# Sheet1.net
KiCad netlist of a schematic drawn in Altium Designer
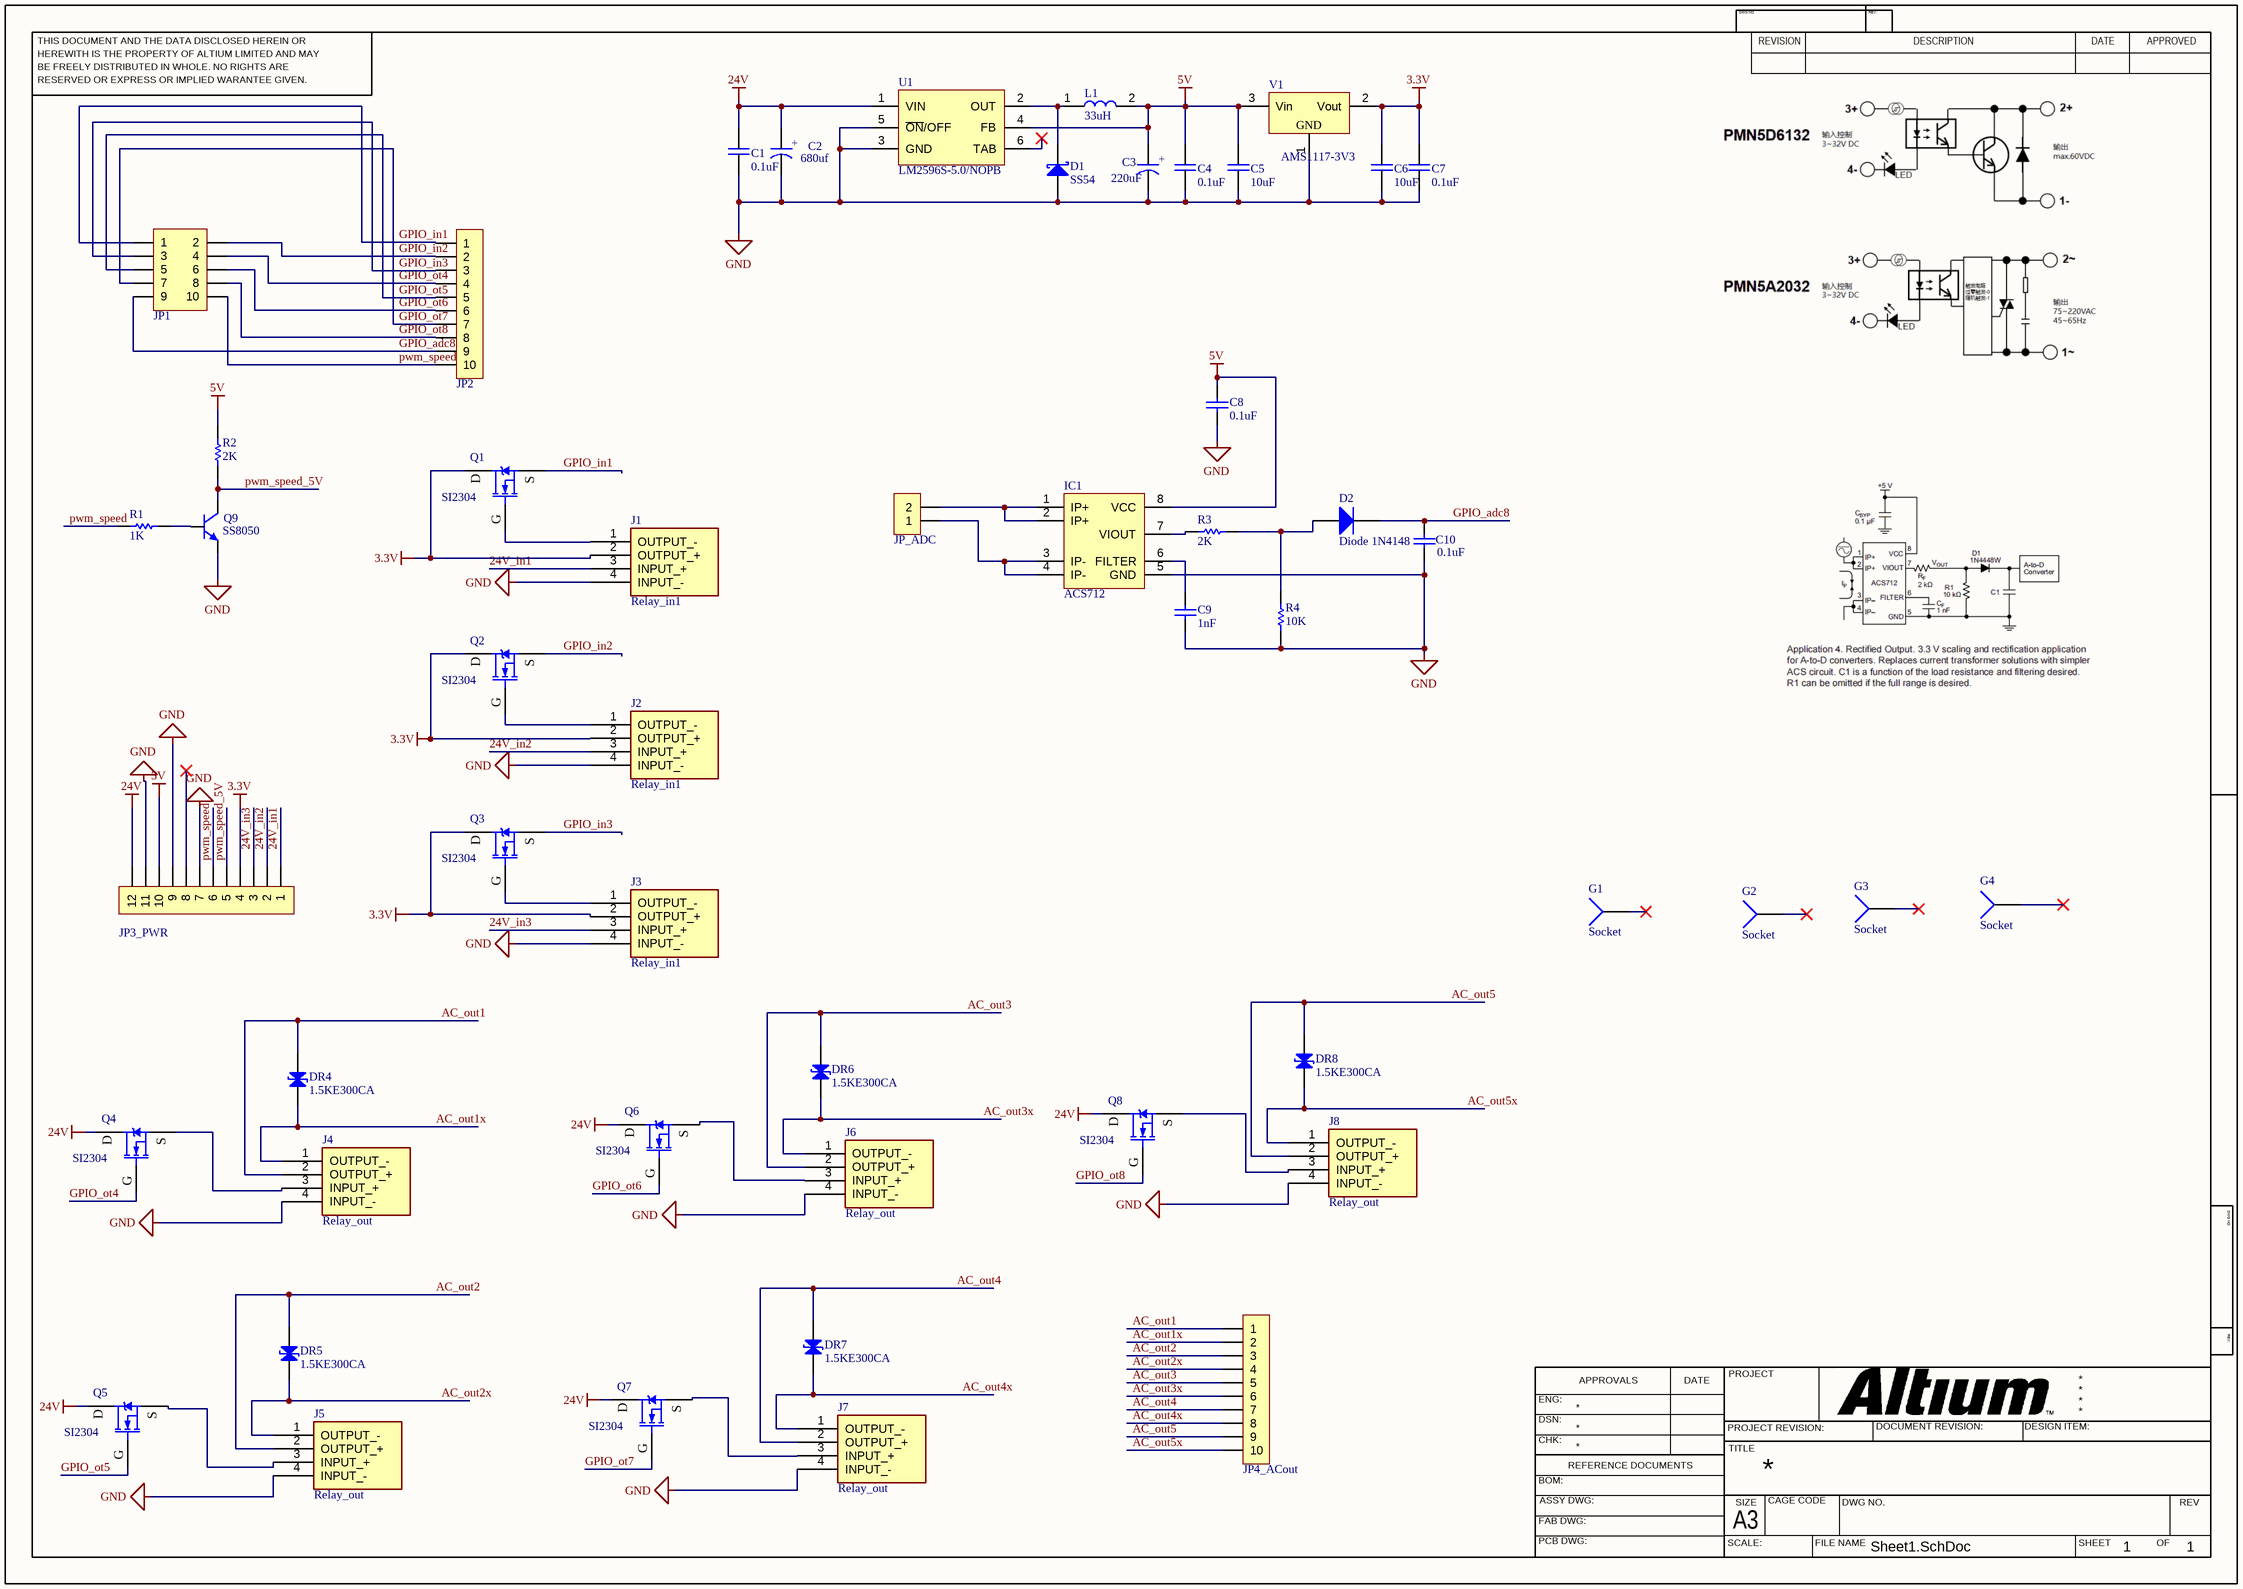
[diagram p0: Sheet1.SchDoc]

(export (version "E")
  (design (tool "Eeschema 10.0.6"))
  (components
    (comp (ref "C1") (value "0.1uF") (footprint "C 0805_M") (libsource (lib "LM2596S_5.0") (part "CAP-SMT")))
    (comp (ref "C2")
      (value "680uf")
      (footprint "CAP 5.0*12.5*20")
      (description "CAP-SMD")
      (libsource (lib "LM2596S_5.0") (part "CAP-SMD"))
    )
    (comp (ref "C3")
      (value "220uF")
      (footprint "CAP 5.0*10*16")
      (description "CAP-SMD")
      (libsource (lib "LM2596S_5.0") (part "CAP-SMD"))
    )
    (comp (ref "C4") (value "0.1uF") (footprint "C 0805_M") (libsource (lib "LM2596S_5.0") (part "CAP-SMT")))
    (comp (ref "C5") (value "10uF") (footprint "C 0805_M") (libsource (lib "LM2596S_5.0") (part "CAP-SMT")))
    (comp (ref "C6") (value "10uF") (footprint "C 0805_M") (libsource (lib "LM2596S_5.0") (part "CAP-SMT")))
    (comp (ref "C7") (value "0.1uF") (footprint "C 0805_M") (libsource (lib "LM2596S_5.0") (part "CAP-SMT")))
    (comp (ref "C8")
      (value "0.1uF")
      (footprint "C 0805_M")
      (description "Capacitor")
      (fields (field (name "PUBLISHER") "Altium Limited"))
      (libsource (lib "Miscellaneous Devices") (part "Cap"))
    )
    (comp (ref "C9")
      (value "1nF")
      (footprint "C 0805_M")
      (description "Capacitor")
      (fields (field (name "PUBLISHER") "Altium Limited"))
      (libsource (lib "Miscellaneous Devices") (part "Cap"))
    )
    (comp (ref "C10")
      (value "0.1uF")
      (footprint "C 0805_M")
      (description "Capacitor")
      (fields (field (name "PUBLISHER") "Altium Limited"))
      (libsource (lib "Miscellaneous Devices") (part "Cap"))
    )
    (comp (ref "D1") (value "SS54") (footprint "SMC") (libsource (lib "LM2596S_5.0") (part "DIO")))
    (comp (ref "D2")
      (value "Diode 1N4148")
      (footprint "SOD-123")
      (description "High Conductance Fast Diode")
      (fields (field (name "PUBLISHER") "Altium Limited"))
      (libsource (lib "Miscellaneous Devices") (part "Diode 1N4148"))
    )
    (comp (ref "DR4")
      (value "1.5KE300CA")
      (footprint "DO-15")
      (description "瞬态电压抑制二极管")
      (fields (field (name "版权归属") "源创客"))
      (libsource (lib "8.1   - 二极管-整流桥") (part "DR"))
    )
    (comp (ref "DR5")
      (value "1.5KE300CA")
      (footprint "DO-15")
      (description "瞬态电压抑制二极管")
      (fields (field (name "版权归属") "源创客"))
      (libsource (lib "8.1   - 二极管-整流桥") (part "DR"))
    )
    (comp (ref "DR6")
      (value "1.5KE300CA")
      (footprint "DO-15")
      (description "瞬态电压抑制二极管")
      (fields (field (name "版权归属") "源创客"))
      (libsource (lib "8.1   - 二极管-整流桥") (part "DR"))
    )
    (comp (ref "DR7")
      (value "1.5KE300CA")
      (footprint "DO-15")
      (description "瞬态电压抑制二极管")
      (fields (field (name "版权归属") "源创客"))
      (libsource (lib "8.1   - 二极管-整流桥") (part "DR"))
    )
    (comp (ref "DR8")
      (value "1.5KE300CA")
      (footprint "DO-15")
      (description "瞬态电压抑制二极管")
      (fields (field (name "版权归属") "源创客"))
      (libsource (lib "8.1   - 二极管-整流桥") (part "DR"))
    )
    (comp (ref "G1")
      (value "Socket")
      (footprint "M3x6_L")
      (fields (field (name "PUBLISHER") "Altium Limited"))
      (libsource (lib "Miscellaneous Connectors") (part "Socket"))
    )
    (comp (ref "G2")
      (value "Socket")
      (footprint "M3x6_L")
      (fields (field (name "PUBLISHER") "Altium Limited"))
      (libsource (lib "Miscellaneous Connectors") (part "Socket"))
    )
    (comp (ref "G3")
      (value "Socket")
      (footprint "M3x6_L")
      (fields (field (name "PUBLISHER") "Altium Limited"))
      (libsource (lib "Miscellaneous Connectors") (part "Socket"))
    )
    (comp (ref "G4")
      (value "Socket")
      (footprint "M3x6_L")
      (fields (field (name "PUBLISHER") "Altium Limited"))
      (libsource (lib "Miscellaneous Connectors") (part "Socket"))
    )
    (comp (ref "IC1")
      (value "ACS712")
      (footprint "SOP8_M")
      (description "电流检测芯片")
      (fields (field (name "版权归属") "源创客"))
      (libsource (lib "1.1   - IC芯片") (part "ACS712"))
    )
    (comp (ref "J1")
      (value "Relay_in1")
      (footprint "2982647")
      (description "Connector")
      (fields
        (field (name "MANUFACTURER_PART_NUMBER") "2982647")
        (field (name "MOUSER PART NUMBER") "651-2982647")
      )
      (libsource (lib "SSR") (part "2982647"))
    )
    (comp (ref "J2")
      (value "Relay_in1")
      (footprint "2982647")
      (description "Connector")
      (fields
        (field (name "MANUFACTURER_PART_NUMBER") "2982647")
        (field (name "MOUSER PART NUMBER") "651-2982647")
      )
      (libsource (lib "SSR") (part "2982647"))
    )
    (comp (ref "J3")
      (value "Relay_in1")
      (footprint "2982647")
      (description "Connector")
      (fields
        (field (name "MANUFACTURER_PART_NUMBER") "2982647")
        (field (name "MOUSER PART NUMBER") "651-2982647")
      )
      (libsource (lib "SSR") (part "2982647"))
    )
    (comp (ref "J4")
      (value "Relay_out")
      (footprint "2982647")
      (description "Connector")
      (fields
        (field (name "MANUFACTURER_PART_NUMBER") "2982647")
        (field (name "MOUSER PART NUMBER") "651-2982647")
      )
      (libsource (lib "SSR") (part "2982647"))
    )
    (comp (ref "J5")
      (value "Relay_out")
      (footprint "2982647")
      (description "Connector")
      (fields
        (field (name "MANUFACTURER_PART_NUMBER") "2982647")
        (field (name "MOUSER PART NUMBER") "651-2982647")
      )
      (libsource (lib "SSR") (part "2982647"))
    )
    (comp (ref "J6")
      (value "Relay_out")
      (footprint "2982647")
      (description "Connector")
      (fields
        (field (name "MANUFACTURER_PART_NUMBER") "2982647")
        (field (name "MOUSER PART NUMBER") "651-2982647")
      )
      (libsource (lib "SSR") (part "2982647"))
    )
    (comp (ref "J7")
      (value "Relay_out")
      (footprint "2982647")
      (description "Connector")
      (fields
        (field (name "MANUFACTURER_PART_NUMBER") "2982647")
        (field (name "MOUSER PART NUMBER") "651-2982647")
      )
      (libsource (lib "SSR") (part "2982647"))
    )
    (comp (ref "J8")
      (value "Relay_out")
      (footprint "2982647")
      (description "Connector")
      (fields
        (field (name "MANUFACTURER_PART_NUMBER") "2982647")
        (field (name "MOUSER PART NUMBER") "651-2982647")
      )
      (libsource (lib "") (part "2982647_1"))
    )
    (comp (ref "JP1")
      (value "Header 5X2")
      (footprint "IDC2.54-LI-2x5P")
      (description "5*2P接插件")
      (fields (field (name "版权归属") "源创客"))
      (libsource (lib "4.5   - 接插件-脚距2.54") (part "Header 5X2"))
    )
    (comp (ref "JP2")
      (value "HDR-1X10")
      (footprint "KF128-3.81-10P")
      (description "10P接插件")
      (fields (field (name "版权归属") "源创客"))
      (libsource (lib "4.6   - 接插件-脚距3.5") (part "Header 10"))
    )
    (comp (ref "JP3_PWR")
      (value "HDR-1X12")
      (footprint "KF128-3.81-12P")
      (description "12P接插件")
      (fields (field (name "版权归属") "源创客"))
      (libsource (lib "4.7   - 接插件-脚距3.81") (part "Header 12"))
    )
    (comp (ref "JP4_ACout")
      (value "HDR-1X10")
      (footprint "KF128-3.81-10P")
      (description "10P接插件")
      (fields (field (name "版权归属") "源创客"))
      (libsource (lib "4.6   - 接插件-脚距3.5") (part "Header 10"))
    )
    (comp (ref "JP_ADC")
      (value "HDR-1X2")
      (footprint "KF128-3.81-2P")
      (description "2P接插件")
      (fields (field (name "版权归属") "源创客"))
      (libsource (lib "4.7   - 接插件-脚距3.81") (part "Header 2"))
    )
    (comp (ref "L1") (value "33uH") (footprint "CDRH74") (libsource (lib "LM2596S_5.0") (part "L-CDRH74")))
    (comp (ref "Q1")
      (value "SI2304")
      (footprint "SOT23-3M")
      (description "N沟道场效应管")
      (fields (field (name "版权归属") "源创客"))
      (libsource (lib "6.1   - 场效应管-可控硅") (part "SI2302"))
    )
    (comp (ref "Q2")
      (value "SI2304")
      (footprint "SOT23-3M")
      (description "N沟道场效应管")
      (fields (field (name "版权归属") "源创客"))
      (libsource (lib "6.1   - 场效应管-可控硅") (part "SI2302"))
    )
    (comp (ref "Q3")
      (value "SI2304")
      (footprint "SOT23-3M")
      (description "N沟道场效应管")
      (fields (field (name "版权归属") "源创客"))
      (libsource (lib "6.1   - 场效应管-可控硅") (part "SI2302"))
    )
    (comp (ref "Q4")
      (value "SI2304")
      (footprint "SOT23-3M")
      (description "N沟道场效应管")
      (fields (field (name "版权归属") "源创客"))
      (libsource (lib "6.1   - 场效应管-可控硅") (part "SI2302"))
    )
    (comp (ref "Q5")
      (value "SI2304")
      (footprint "SOT23-3M")
      (description "N沟道场效应管")
      (fields (field (name "版权归属") "源创客"))
      (libsource (lib "6.1   - 场效应管-可控硅") (part "SI2302"))
    )
    (comp (ref "Q6")
      (value "SI2304")
      (footprint "SOT23-3M")
      (description "N沟道场效应管")
      (fields (field (name "版权归属") "源创客"))
      (libsource (lib "6.1   - 场效应管-可控硅") (part "SI2302"))
    )
    (comp (ref "Q7")
      (value "SI2304")
      (footprint "SOT23-3M")
      (description "N沟道场效应管")
      (fields (field (name "版权归属") "源创客"))
      (libsource (lib "6.1   - 场效应管-可控硅") (part "SI2302"))
    )
    (comp (ref "Q8")
      (value "SI2304")
      (footprint "SOT23-3M")
      (description "N沟道场效应管")
      (fields (field (name "版权归属") "源创客"))
      (libsource (lib "6.1   - 场效应管-可控硅") (part "SI2302"))
    )
    (comp (ref "Q9")
      (value "SS8050")
      (footprint "TO92A")
      (description "高频放大-NPN型")
      (fields (field (name "版权归属") "源创客"))
      (libsource (lib "6.2   - 三极管") (part "8050-DIP"))
    )
    (comp (ref "R1")
      (value "1K")
      (footprint "R 0805_M")
      (description "Resistor")
      (fields (field (name "PUBLISHER") "Altium Limited"))
      (libsource (lib "Miscellaneous Devices") (part "Res1"))
    )
    (comp (ref "R2")
      (value "2K")
      (footprint "R 0805_M")
      (description "Resistor")
      (fields (field (name "PUBLISHER") "Altium Limited"))
      (libsource (lib "Miscellaneous Devices") (part "Res1"))
    )
    (comp (ref "R3")
      (value "2K")
      (footprint "R 0805_M")
      (description "Resistor")
      (fields (field (name "PUBLISHER") "Altium Limited"))
      (libsource (lib "Miscellaneous Devices") (part "Res1"))
    )
    (comp (ref "R4")
      (value "10K")
      (footprint "R 0805_M")
      (description "Resistor")
      (fields (field (name "PUBLISHER") "Altium Limited"))
      (libsource (lib "Miscellaneous Devices") (part "Res1"))
    )
    (comp (ref "U1")
      (value "LM2596S-5.0/NOPB")
      (footprint "TO263-5A")
      (description "SIMPLE SWITCHER® Power Converter 150 KHz 3A Step-Down Voltage Regulator, 5-pin TO-263, Pb-Free")
      (fields (field (name "MANUFACTURER") "Texas Instruments"))
      (libsource (lib "LM2596S_5.0") (part "LM2596S-5.0"))
    )
    (comp (ref "V1")
      (value "AMS1117-3V3")
      (footprint "SOT223_M")
      (description "三端稳压芯片")
      (fields (field (name "版权归属") "源创客"))
      (libsource (lib "1.3   - 电源类芯片") (part "AMS1117"))
    )
  )
  (nets
    (net (code "1") (name "/24V_in1") (class "Default")
      (node (ref "J1") (pin "3") (pinfunction "INPUT_+_3") (pintype "passive"))
      (node (ref "JP3_PWR") (pin "1") (pinfunction "1_1") (pintype "passive"))
    )
    (net (code "2") (name "/24V_in2") (class "Default")
      (node (ref "J2") (pin "3") (pinfunction "INPUT_+_3") (pintype "passive"))
      (node (ref "JP3_PWR") (pin "2") (pinfunction "2_2") (pintype "passive"))
    )
    (net (code "3") (name "/24V_in3") (class "Default")
      (node (ref "J3") (pin "3") (pinfunction "INPUT_+_3") (pintype "passive"))
      (node (ref "JP3_PWR") (pin "3") (pinfunction "3_3") (pintype "passive"))
    )
    (net (code "4") (name "/AC_out1") (class "Default")
      (node (ref "DR4") (pin "1") (pinfunction "A_1") (pintype "passive"))
      (node (ref "J4") (pin "2") (pinfunction "OUTPUT_+_2") (pintype "passive"))
      (node (ref "JP4_ACout") (pin "1") (pinfunction "1_1") (pintype "passive"))
    )
    (net (code "5") (name "/AC_out1x") (class "Default")
      (node (ref "DR4") (pin "2") (pinfunction "K_2") (pintype "passive"))
      (node (ref "J4") (pin "1") (pinfunction "OUTPUT_-_1") (pintype "passive"))
      (node (ref "JP4_ACout") (pin "2") (pinfunction "2_2") (pintype "passive"))
    )
    (net (code "6") (name "/AC_out2") (class "Default")
      (node (ref "DR5") (pin "1") (pinfunction "A_1") (pintype "passive"))
      (node (ref "J5") (pin "2") (pinfunction "OUTPUT_+_2") (pintype "passive"))
      (node (ref "JP4_ACout") (pin "3") (pinfunction "3_3") (pintype "passive"))
    )
    (net (code "7") (name "/AC_out2x") (class "Default")
      (node (ref "DR5") (pin "2") (pinfunction "K_2") (pintype "passive"))
      (node (ref "J5") (pin "1") (pinfunction "OUTPUT_-_1") (pintype "passive"))
      (node (ref "JP4_ACout") (pin "4") (pinfunction "4_4") (pintype "passive"))
    )
    (net (code "8") (name "/AC_out3") (class "Default")
      (node (ref "DR6") (pin "1") (pinfunction "A_1") (pintype "passive"))
      (node (ref "J6") (pin "2") (pinfunction "OUTPUT_+_2") (pintype "passive"))
      (node (ref "JP4_ACout") (pin "5") (pinfunction "5_5") (pintype "passive"))
    )
    (net (code "9") (name "/AC_out3x") (class "Default")
      (node (ref "DR6") (pin "2") (pinfunction "K_2") (pintype "passive"))
      (node (ref "J6") (pin "1") (pinfunction "OUTPUT_-_1") (pintype "passive"))
      (node (ref "JP4_ACout") (pin "6") (pinfunction "6_6") (pintype "passive"))
    )
    (net (code "10") (name "/AC_out4") (class "Default")
      (node (ref "DR7") (pin "1") (pinfunction "A_1") (pintype "passive"))
      (node (ref "J7") (pin "2") (pinfunction "OUTPUT_+_2") (pintype "passive"))
      (node (ref "JP4_ACout") (pin "7") (pinfunction "7_7") (pintype "passive"))
    )
    (net (code "11") (name "/AC_out4x") (class "Default")
      (node (ref "DR7") (pin "2") (pinfunction "K_2") (pintype "passive"))
      (node (ref "J7") (pin "1") (pinfunction "OUTPUT_-_1") (pintype "passive"))
      (node (ref "JP4_ACout") (pin "8") (pinfunction "8_8") (pintype "passive"))
    )
    (net (code "12") (name "/AC_out5") (class "Default")
      (node (ref "DR8") (pin "1") (pinfunction "A_1") (pintype "passive"))
      (node (ref "J8") (pin "2") (pinfunction "OUTPUT_+_2") (pintype "passive"))
      (node (ref "JP4_ACout") (pin "9") (pinfunction "9_9") (pintype "passive"))
    )
    (net (code "13") (name "/AC_out5x") (class "Default")
      (node (ref "DR8") (pin "2") (pinfunction "K_2") (pintype "passive"))
      (node (ref "J8") (pin "1") (pinfunction "OUTPUT_-_1") (pintype "passive"))
      (node (ref "JP4_ACout") (pin "10") (pinfunction "10_10") (pintype "passive"))
    )
    (net (code "14") (name "/GPIO_adc8") (class "Default")
      (node (ref "C10") (pin "2") (pinfunction "2_2") (pintype "passive"))
      (node (ref "D2") (pin "2") (pinfunction "K_2") (pintype "passive"))
      (node (ref "JP1") (pin "9") (pinfunction "9_9") (pintype "passive"))
      (node (ref "JP2") (pin "9") (pinfunction "9_9") (pintype "passive"))
    )
    (net (code "15") (name "/GPIO_in1") (class "Default")
      (node (ref "JP1") (pin "1") (pinfunction "1_1") (pintype "passive"))
      (node (ref "JP2") (pin "1") (pinfunction "1_1") (pintype "passive"))
      (node (ref "Q1") (pin "2") (pinfunction "S_2") (pintype "passive"))
    )
    (net (code "16") (name "/GPIO_in2") (class "Default")
      (node (ref "JP1") (pin "2") (pinfunction "2_2") (pintype "passive"))
      (node (ref "JP2") (pin "2") (pinfunction "2_2") (pintype "passive"))
      (node (ref "Q2") (pin "2") (pinfunction "S_2") (pintype "passive"))
    )
    (net (code "17") (name "/GPIO_in3") (class "Default")
      (node (ref "JP1") (pin "3") (pinfunction "3_3") (pintype "passive"))
      (node (ref "JP2") (pin "3") (pinfunction "3_3") (pintype "passive"))
      (node (ref "Q3") (pin "2") (pinfunction "S_2") (pintype "passive"))
    )
    (net (code "18") (name "/GPIO_ot4") (class "Default")
      (node (ref "JP1") (pin "4") (pinfunction "4_4") (pintype "passive"))
      (node (ref "JP2") (pin "4") (pinfunction "4_4") (pintype "passive"))
      (node (ref "Q4") (pin "1") (pinfunction "G_1") (pintype "passive"))
    )
    (net (code "19") (name "/GPIO_ot5") (class "Default")
      (node (ref "JP1") (pin "5") (pinfunction "5_5") (pintype "passive"))
      (node (ref "JP2") (pin "5") (pinfunction "5_5") (pintype "passive"))
      (node (ref "Q5") (pin "1") (pinfunction "G_1") (pintype "passive"))
    )
    (net (code "20") (name "/GPIO_ot6") (class "Default")
      (node (ref "JP1") (pin "6") (pinfunction "6_6") (pintype "passive"))
      (node (ref "JP2") (pin "6") (pinfunction "6_6") (pintype "passive"))
      (node (ref "Q6") (pin "1") (pinfunction "G_1") (pintype "passive"))
    )
    (net (code "21") (name "/GPIO_ot7") (class "Default")
      (node (ref "JP1") (pin "7") (pinfunction "7_7") (pintype "passive"))
      (node (ref "JP2") (pin "7") (pinfunction "7_7") (pintype "passive"))
      (node (ref "Q7") (pin "1") (pinfunction "G_1") (pintype "passive"))
    )
    (net (code "22") (name "/GPIO_ot8") (class "Default")
      (node (ref "JP1") (pin "8") (pinfunction "8_8") (pintype "passive"))
      (node (ref "JP2") (pin "8") (pinfunction "8_8") (pintype "passive"))
      (node (ref "Q8") (pin "1") (pinfunction "G_1") (pintype "passive"))
    )
    (net (code "23") (name "/pwm_speed") (class "Default")
      (node (ref "JP1") (pin "10") (pinfunction "10_10") (pintype "passive"))
      (node (ref "JP2") (pin "10") (pinfunction "10_10") (pintype "passive"))
      (node (ref "JP3_PWR") (pin "6") (pinfunction "6_6") (pintype "passive"))
      (node (ref "R1") (pin "1") (pinfunction "1_1") (pintype "passive"))
    )
    (net (code "24") (name "/pwm_speed_5V") (class "Default")
      (node (ref "JP3_PWR") (pin "5") (pinfunction "5_5") (pintype "passive"))
      (node (ref "Q9") (pin "3") (pinfunction "C_3") (pintype "passive"))
      (node (ref "R2") (pin "1") (pinfunction "1_1") (pintype "passive"))
    )
    (net (code "25") (name "3.3V") (class "Default")
      (node (ref "C6") (pin "2") (pinfunction "2_2") (pintype "passive"))
      (node (ref "C7") (pin "2") (pinfunction "2_2") (pintype "passive"))
      (node (ref "J1") (pin "2") (pinfunction "OUTPUT_+_2") (pintype "passive"))
      (node (ref "J2") (pin "2") (pinfunction "OUTPUT_+_2") (pintype "passive"))
      (node (ref "J3") (pin "2") (pinfunction "OUTPUT_+_2") (pintype "passive"))
      (node (ref "JP3_PWR") (pin "4") (pinfunction "4_4") (pintype "passive"))
      (node (ref "Q1") (pin "3") (pinfunction "D_3") (pintype "passive"))
      (node (ref "Q2") (pin "3") (pinfunction "D_3") (pintype "passive"))
      (node (ref "Q3") (pin "3") (pinfunction "D_3") (pintype "passive"))
      (node (ref "V1") (pin "2") (pinfunction "Vout_2") (pintype "passive"))
    )
    (net (code "26") (name "5V") (class "Default")
      (node (ref "C3") (pin "2") (pinfunction "2_2") (pintype "passive"))
      (node (ref "C4") (pin "2") (pinfunction "2_2") (pintype "passive"))
      (node (ref "C5") (pin "2") (pinfunction "2_2") (pintype "passive"))
      (node (ref "C8") (pin "2") (pinfunction "2_2") (pintype "passive"))
      (node (ref "IC1") (pin "8") (pinfunction "VCC_8") (pintype "passive"))
      (node (ref "JP3_PWR") (pin "10") (pinfunction "10_10") (pintype "passive"))
      (node (ref "L1") (pin "2") (pinfunction "2_2") (pintype "passive"))
      (node (ref "R2") (pin "2") (pinfunction "2_2") (pintype "passive"))
      (node (ref "U1") (pin "4") (pinfunction "FB_4") (pintype "passive"))
      (node (ref "V1") (pin "3") (pinfunction "Vin_3") (pintype "passive"))
    )
    (net (code "27") (name "24V") (class "Default")
      (node (ref "C1") (pin "2") (pinfunction "2_2") (pintype "passive"))
      (node (ref "C2") (pin "2") (pinfunction "2_2") (pintype "passive"))
      (node (ref "JP3_PWR") (pin "12") (pinfunction "12_12") (pintype "passive"))
      (node (ref "Q4") (pin "3") (pinfunction "D_3") (pintype "passive"))
      (node (ref "Q5") (pin "3") (pinfunction "D_3") (pintype "passive"))
      (node (ref "Q6") (pin "3") (pinfunction "D_3") (pintype "passive"))
      (node (ref "Q7") (pin "3") (pinfunction "D_3") (pintype "passive"))
      (node (ref "Q8") (pin "3") (pinfunction "D_3") (pintype "passive"))
      (node (ref "U1") (pin "1") (pinfunction "VIN_1") (pintype "power_in"))
    )
    (net (code "28") (name "GND") (class "Default")
      (node (ref "C1") (pin "1") (pinfunction "1_1") (pintype "passive"))
      (node (ref "C10") (pin "1") (pinfunction "1_1") (pintype "passive"))
      (node (ref "C2") (pin "1") (pinfunction "1_1") (pintype "passive"))
      (node (ref "C3") (pin "1") (pinfunction "1_1") (pintype "passive"))
      (node (ref "C4") (pin "1") (pinfunction "1_1") (pintype "passive"))
      (node (ref "C5") (pin "1") (pinfunction "1_1") (pintype "passive"))
      (node (ref "C6") (pin "1") (pinfunction "1_1") (pintype "passive"))
      (node (ref "C7") (pin "1") (pinfunction "1_1") (pintype "passive"))
      (node (ref "C8") (pin "1") (pinfunction "1_1") (pintype "passive"))
      (node (ref "C9") (pin "1") (pinfunction "1_1") (pintype "passive"))
      (node (ref "D1") (pin "1") (pinfunction "1_1") (pintype "passive"))
      (node (ref "IC1") (pin "5") (pinfunction "GND_5") (pintype "passive"))
      (node (ref "J1") (pin "4") (pinfunction "INPUT_-_4") (pintype "passive"))
      (node (ref "J2") (pin "4") (pinfunction "INPUT_-_4") (pintype "passive"))
      (node (ref "J3") (pin "4") (pinfunction "INPUT_-_4") (pintype "passive"))
      (node (ref "J4") (pin "4") (pinfunction "INPUT_-_4") (pintype "passive"))
      (node (ref "J5") (pin "4") (pinfunction "INPUT_-_4") (pintype "passive"))
      (node (ref "J6") (pin "4") (pinfunction "INPUT_-_4") (pintype "passive"))
      (node (ref "J7") (pin "4") (pinfunction "INPUT_-_4") (pintype "passive"))
      (node (ref "J8") (pin "4") (pinfunction "INPUT_-_4") (pintype "passive"))
      (node (ref "JP3_PWR") (pin "11") (pinfunction "11_11") (pintype "passive"))
      (node (ref "JP3_PWR") (pin "7") (pinfunction "7_7") (pintype "passive"))
      (node (ref "JP3_PWR") (pin "9") (pinfunction "9_9") (pintype "passive"))
      (node (ref "Q9") (pin "1") (pinfunction "E_1") (pintype "passive"))
      (node (ref "R4") (pin "1") (pinfunction "1_1") (pintype "passive"))
      (node (ref "U1") (pin "3") (pinfunction "GND_3") (pintype "power_in"))
      (node (ref "U1") (pin "5") (pinfunction "~{ON}/OFF_5") (pintype "passive"))
      (node (ref "V1") (pin "1") (pinfunction "GND_1") (pintype "passive"))
    )
    (net (code "29") (name "Net-(D2-A)") (class "Default")
      (node (ref "D2") (pin "1") (pinfunction "A_1") (pintype "passive"))
      (node (ref "R3") (pin "2") (pinfunction "2_2") (pintype "passive"))
      (node (ref "R4") (pin "2") (pinfunction "2_2") (pintype "passive"))
    )
    (net (code "30") (name "Net-(IC1-FILTER)") (class "Default")
      (node (ref "C9") (pin "2") (pinfunction "2_2") (pintype "passive"))
      (node (ref "IC1") (pin "6") (pinfunction "FILTER_6") (pintype "passive"))
    )
    (net (code "31") (name "Net-(IC1-IP+-Pad1)") (class "Default")
      (node (ref "IC1") (pin "1") (pinfunction "IP+_1") (pintype "passive"))
      (node (ref "IC1") (pin "2") (pinfunction "IP+_2") (pintype "passive"))
      (node (ref "JP_ADC") (pin "2") (pinfunction "2_2") (pintype "passive"))
    )
    (net (code "32") (name "Net-(IC1-IP--Pad3)") (class "Default")
      (node (ref "IC1") (pin "3") (pinfunction "IP-_3") (pintype "passive"))
      (node (ref "IC1") (pin "4") (pinfunction "IP-_4") (pintype "passive"))
      (node (ref "JP_ADC") (pin "1") (pinfunction "1_1") (pintype "passive"))
    )
    (net (code "33") (name "Net-(IC1-VIOUT)") (class "Default")
      (node (ref "IC1") (pin "7") (pinfunction "VIOUT_7") (pintype "passive"))
      (node (ref "R3") (pin "1") (pinfunction "1_1") (pintype "passive"))
    )
    (net (code "34") (name "Net-(J1-OUTPUT_-)") (class "Default")
      (node (ref "J1") (pin "1") (pinfunction "OUTPUT_-_1") (pintype "passive"))
      (node (ref "Q1") (pin "1") (pinfunction "G_1") (pintype "passive"))
    )
    (net (code "35") (name "Net-(J2-OUTPUT_-)") (class "Default")
      (node (ref "J2") (pin "1") (pinfunction "OUTPUT_-_1") (pintype "passive"))
      (node (ref "Q2") (pin "1") (pinfunction "G_1") (pintype "passive"))
    )
    (net (code "36") (name "Net-(J3-OUTPUT_-)") (class "Default")
      (node (ref "J3") (pin "1") (pinfunction "OUTPUT_-_1") (pintype "passive"))
      (node (ref "Q3") (pin "1") (pinfunction "G_1") (pintype "passive"))
    )
    (net (code "37") (name "Net-(J4-INPUT_+)") (class "Default")
      (node (ref "J4") (pin "3") (pinfunction "INPUT_+_3") (pintype "passive"))
      (node (ref "Q4") (pin "2") (pinfunction "S_2") (pintype "passive"))
    )
    (net (code "38") (name "Net-(J5-INPUT_+)") (class "Default")
      (node (ref "J5") (pin "3") (pinfunction "INPUT_+_3") (pintype "passive"))
      (node (ref "Q5") (pin "2") (pinfunction "S_2") (pintype "passive"))
    )
    (net (code "39") (name "Net-(J6-INPUT_+)") (class "Default")
      (node (ref "J6") (pin "3") (pinfunction "INPUT_+_3") (pintype "passive"))
      (node (ref "Q6") (pin "2") (pinfunction "S_2") (pintype "passive"))
    )
    (net (code "40") (name "Net-(J7-INPUT_+)") (class "Default")
      (node (ref "J7") (pin "3") (pinfunction "INPUT_+_3") (pintype "passive"))
      (node (ref "Q7") (pin "2") (pinfunction "S_2") (pintype "passive"))
    )
    (net (code "41") (name "Net-(J8-INPUT_+)") (class "Default")
      (node (ref "J8") (pin "3") (pinfunction "INPUT_+_3") (pintype "passive"))
      (node (ref "Q8") (pin "2") (pinfunction "S_2") (pintype "passive"))
    )
    (net (code "42") (name "Net-(Q9-B)") (class "Default")
      (node (ref "Q9") (pin "2") (pinfunction "B_2") (pintype "passive"))
      (node (ref "R1") (pin "2") (pinfunction "2_2") (pintype "passive"))
    )
    (net (code "43") (name "Net-(U1-OUT)") (class "Default")
      (node (ref "D1") (pin "2") (pinfunction "2_2") (pintype "passive"))
      (node (ref "L1") (pin "1") (pinfunction "1_1") (pintype "passive"))
      (node (ref "U1") (pin "2") (pinfunction "OUT_2") (pintype "power_in"))
    )
    (net (code "44") (name "unconnected-(G1-Pad1)") (class "Default")
      (node (ref "G1") (pin "1") (pinfunction "1_1") (pintype "passive+no_connect"))
    )
    (net (code "45") (name "unconnected-(G2-Pad1)") (class "Default")
      (node (ref "G2") (pin "1") (pinfunction "1_1") (pintype "passive+no_connect"))
    )
    (net (code "46") (name "unconnected-(G3-Pad1)") (class "Default")
      (node (ref "G3") (pin "1") (pinfunction "1_1") (pintype "passive+no_connect"))
    )
    (net (code "47") (name "unconnected-(G4-Pad1)") (class "Default")
      (node (ref "G4") (pin "1") (pinfunction "1_1") (pintype "passive+no_connect"))
    )
    (net (code "48") (name "unconnected-(JP3_PWR-Pad8)") (class "Default")
      (node (ref "JP3_PWR") (pin "8") (pinfunction "8_8") (pintype "passive+no_connect"))
    )
    (net (code "49") (name "unconnected-(U1-TAB-Pad6)") (class "Default")
      (node (ref "U1") (pin "6") (pinfunction "TAB_6") (pintype "power_in+no_connect"))
    )
  )
)
